# esp32_lolin_clone.net
KiCad netlist of a schematic drawn in EAGLE
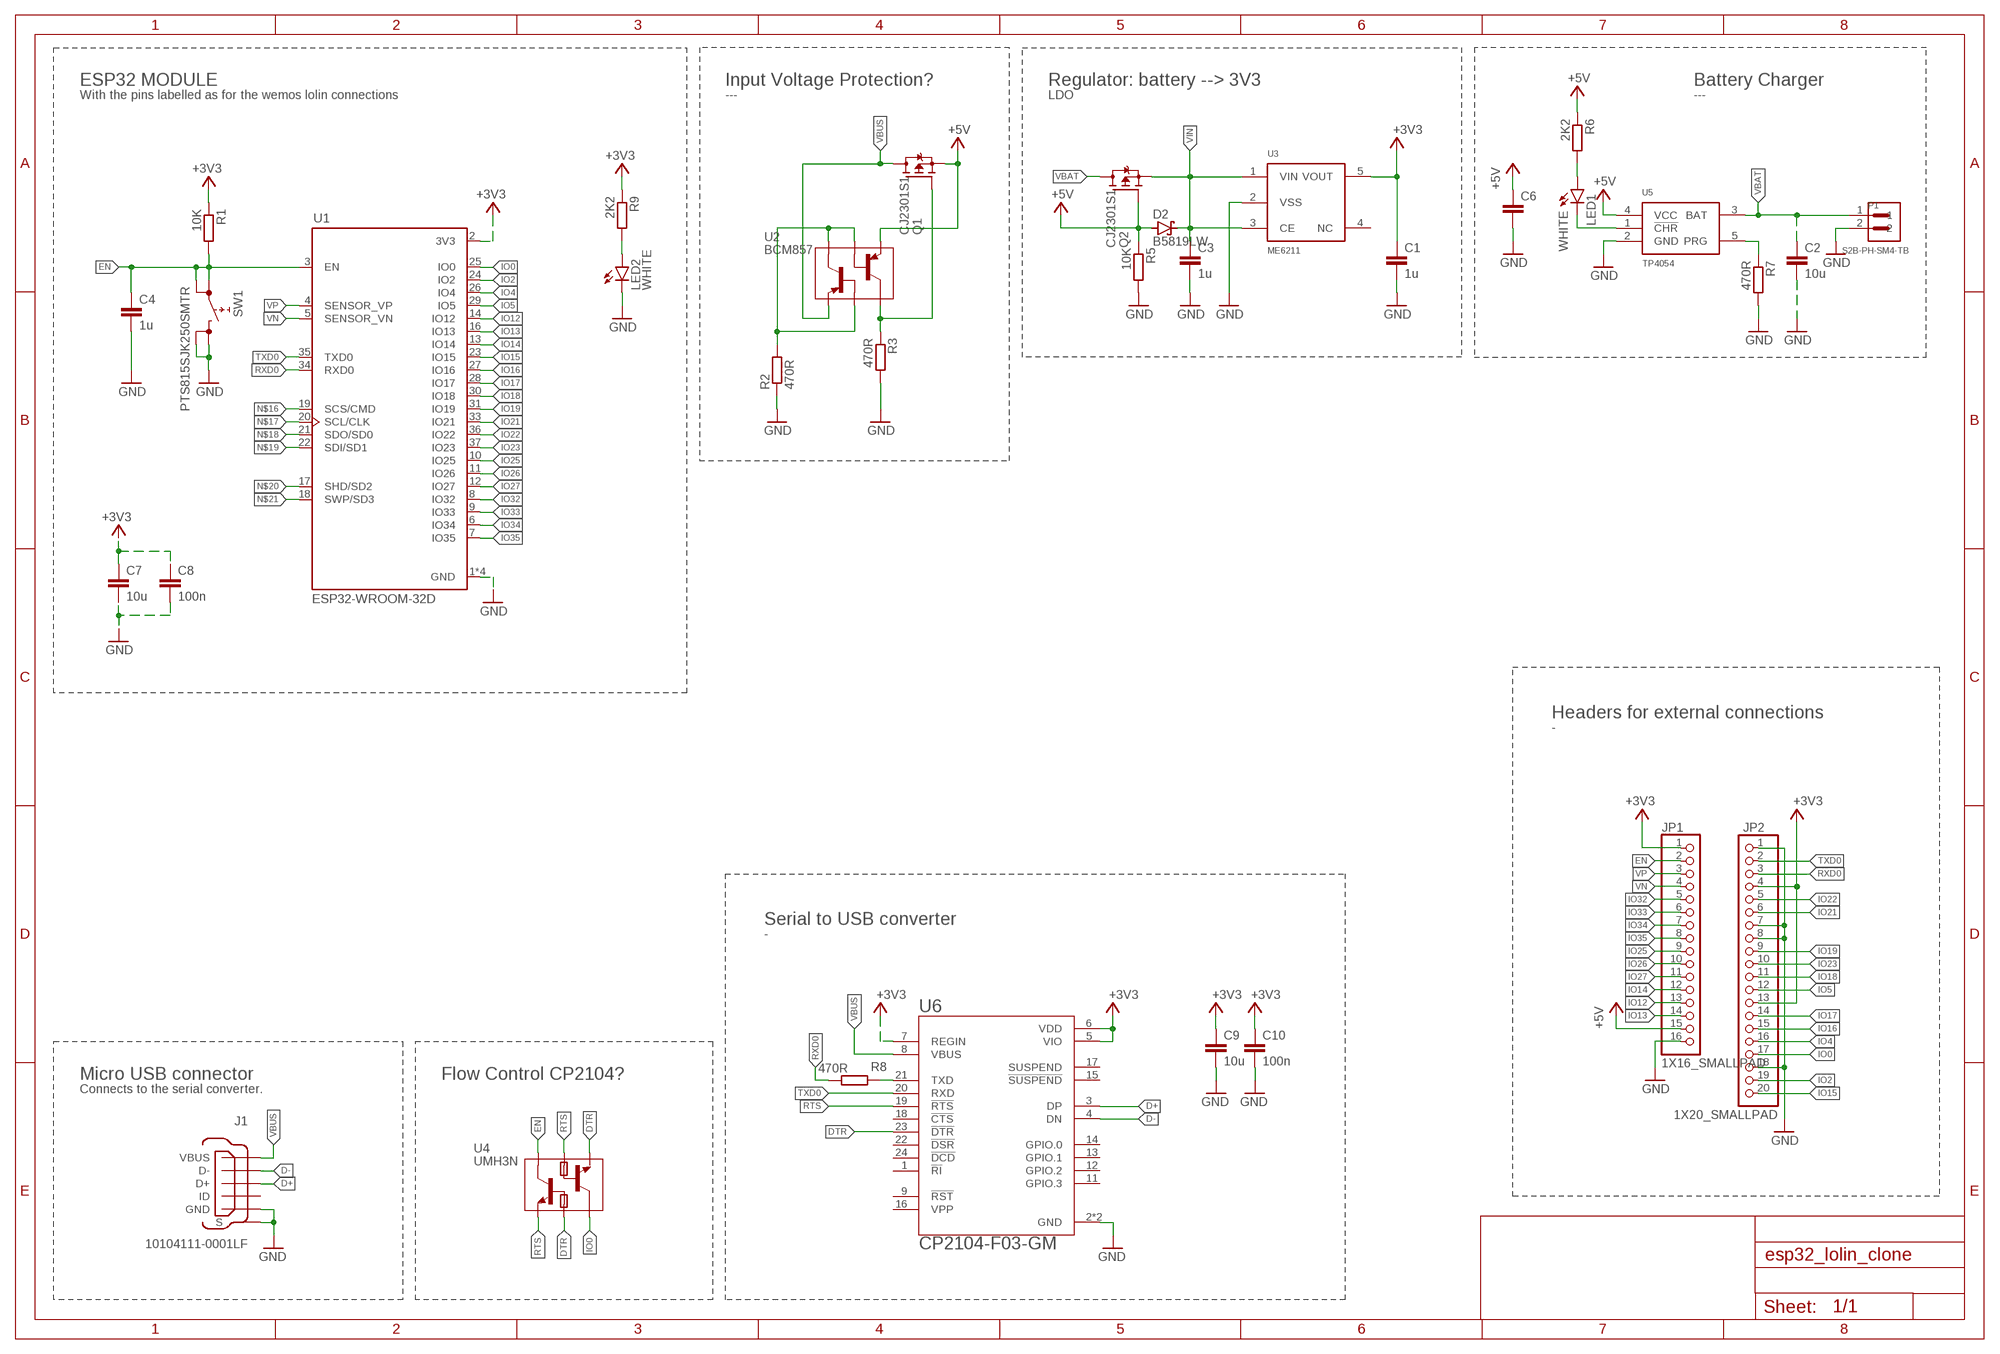
[diagram p0: schematic, sheet 1]

(export (version "E")
  (design (tool "Eeschema 10.0.6"))
  (components
    (comp (ref "C1")
      (value "1u")
      (footprint "eagle-import:C0603K")
      (libsource (lib "eagle-import") (part "C-EUC0603K"))
    )
    (comp (ref "C2")
      (value "10u")
      (footprint "eagle-import:C0603K")
      (libsource (lib "eagle-import") (part "C-EUC0603K"))
    )
    (comp (ref "C3")
      (value "1u")
      (footprint "eagle-import:C0603K")
      (libsource (lib "eagle-import") (part "C-EUC0603K"))
    )
    (comp (ref "C4")
      (value "1u")
      (footprint "eagle-import:C0603K")
      (libsource (lib "eagle-import") (part "C-EUC0603K"))
    )
    (comp (ref "C6")
      (value "C-EUC0603K")
      (footprint "eagle-import:C0603K")
      (libsource (lib "eagle-import") (part "C-EUC0603K"))
    )
    (comp (ref "C7")
      (value "10u")
      (footprint "eagle-import:C0603K")
      (libsource (lib "eagle-import") (part "C-EUC0603K"))
    )
    (comp (ref "C8")
      (value "100n")
      (footprint "eagle-import:C0603K")
      (libsource (lib "eagle-import") (part "C-EUC0603K"))
    )
    (comp (ref "C9")
      (value "10u")
      (footprint "eagle-import:C0603K")
      (libsource (lib "eagle-import") (part "C-EUC0603K"))
    )
    (comp (ref "C10")
      (value "100n")
      (footprint "eagle-import:C0603K")
      (libsource (lib "eagle-import") (part "C-EUC0603K"))
    )
    (comp (ref "D2")
      (value "B5819LW")
      (footprint "eagle-import:SOD123")
      (fields (field (name "MANUFACTURER") "Guangdong Hottech"))
      (libsource (lib "eagle-import") (part "B5819LW"))
    )
    (comp (ref "J1")
      (value "10104111-0001LF")
      (footprint "eagle-import:FRAMATOME_10104111-0001LF")
      (fields (field (name "MANUFACTURER") "Amphenol ICC"))
      (libsource (lib "eagle-import") (part "10104111-0001LF"))
    )
    (comp (ref "JP1")
      (value "1X16_SMALLPAD")
      (footprint "eagle-import:1X16")
      (libsource (lib "eagle-import") (part "1X16_SMALLPAD"))
    )
    (comp (ref "JP2")
      (value "1X20_SMALLPAD")
      (footprint "eagle-import:1X20")
      (libsource (lib "eagle-import") (part "1X20_SMALLPAD"))
    )
    (comp (ref "LED1")
      (value "WHITE")
      (footprint "eagle-import:CHIP-LED0603")
      (libsource (lib "eagle-import") (part "LEDCHIP-LED0603"))
    )
    (comp (ref "LED2")
      (value "WHITE")
      (footprint "eagle-import:CHIP-LED0603")
      (libsource (lib "eagle-import") (part "LEDCHIP-LED0603"))
    )
    (comp (ref "P1")
      (value "S2B-PH-SM4-TB")
      (footprint "eagle-import:JST_S2B-PH-SM4-TB")
      (fields (field (name "MANUFACTURER") "JST Sales"))
      (libsource (lib "eagle-import") (part "S2B-PH-SM4-TB"))
    )
    (comp (ref "Q1")
      (value "CJ2301S1")
      (footprint "eagle-import:SOT23")
      (fields (field (name "MANUFACTURER") "Changjiang Electronics Tech"))
      (libsource (lib "eagle-import") (part "CJ2301S1"))
    )
    (comp (ref "Q2")
      (value "CJ2301S1")
      (footprint "eagle-import:SOT23")
      (fields (field (name "MANUFACTURER") "Changjiang Electronics Tech"))
      (libsource (lib "eagle-import") (part "CJ2301S1"))
    )
    (comp (ref "R1")
      (value "10K")
      (footprint "eagle-import:R0603")
      (libsource (lib "eagle-import") (part "R-EU_R0603"))
    )
    (comp (ref "R2")
      (value "470R")
      (footprint "eagle-import:R0603")
      (libsource (lib "eagle-import") (part "R-EU_R0603"))
    )
    (comp (ref "R3")
      (value "470R")
      (footprint "eagle-import:R0603")
      (libsource (lib "eagle-import") (part "R-EU_R0603"))
    )
    (comp (ref "R5")
      (value "10K")
      (footprint "eagle-import:R0603")
      (libsource (lib "eagle-import") (part "R-EU_R0603"))
    )
    (comp (ref "R6")
      (value "2K2")
      (footprint "eagle-import:R0603")
      (libsource (lib "eagle-import") (part "R-EU_R0603"))
    )
    (comp (ref "R7")
      (value "470R")
      (footprint "eagle-import:R0603")
      (libsource (lib "eagle-import") (part "R-EU_R0603"))
    )
    (comp (ref "R8")
      (value "470R")
      (footprint "eagle-import:R0603")
      (libsource (lib "eagle-import") (part "R-EU_R0603"))
    )
    (comp (ref "R9")
      (value "2K2")
      (footprint "eagle-import:R0603")
      (libsource (lib "eagle-import") (part "R-EU_R0603"))
    )
    (comp (ref "SW1")
      (value "PTS815SJK250SMTR")
      (footprint "eagle-import:PTS815SJK250SMTR")
      (fields (field (name "MANUFACTURER") "C&K"))
      (libsource (lib "eagle-import") (part "PTS815SJK250SMTR"))
    )
    (comp (ref "U1")
      (value "ESP32-WROOM-32D")
      (footprint "eagle-import:MODULE_ESP32-WROOM-32D")
      (fields (field (name "MANUFACTURER") "Espressif Systems"))
      (libsource (lib "eagle-import") (part "ESP32-WROOM-32D"))
    )
    (comp (ref "U2")
      (value "BCM857")
      (footprint "eagle-import:SOT363_INFINEON")
      (fields (field (name "MANUFACTURER") "Nexperia"))
      (libsource (lib "eagle-import") (part "BCM857"))
    )
    (comp (ref "U3")
      (value "ME6211")
      (footprint "eagle-import:SOT23-5")
      (fields (field (name "MANUFACTURER") "MICRONE"))
      (libsource (lib "eagle-import") (part "ME6211"))
    )
    (comp (ref "U4")
      (value "UMH3N")
      (footprint "eagle-import:SOT363_INFINEON")
      (fields (field (name "MANUFACTURER") "Rohm"))
      (libsource (lib "eagle-import") (part "UMH3N"))
    )
    (comp (ref "U5")
      (value "TP4054")
      (footprint "eagle-import:SOT23-5")
      (fields (field (name "MANUFACTURER") "TOPPOWER"))
      (libsource (lib "eagle-import") (part "TP4054"))
    )
    (comp (ref "U6")
      (value "CP2104-F03-GM")
      (footprint "eagle-import:QFN50P400X400X80-25N")
      (fields (field (name "MANUFACTURER") "Silabs"))
      (libsource (lib "eagle-import") (part "CP2104-F03-GM"))
    )
  )
  (nets
    (net (code "1") (name "+3V3") (class "Default")
      (node (ref "C1") (pin "1") (pinfunction "1_1") (pintype "passive"))
      (node (ref "C10") (pin "1") (pinfunction "1_1") (pintype "passive"))
      (node (ref "C7") (pin "1") (pinfunction "1_1") (pintype "passive"))
      (node (ref "C8") (pin "1") (pinfunction "1_1") (pintype "passive"))
      (node (ref "C9") (pin "1") (pinfunction "1_1") (pintype "passive"))
      (node (ref "JP1") (pin "1") (pinfunction "1_1") (pintype "passive"))
      (node (ref "JP2") (pin "13") (pinfunction "13_13") (pintype "passive"))
      (node (ref "JP2") (pin "4") (pinfunction "4_4") (pintype "passive"))
      (node (ref "R1") (pin "1") (pinfunction "1_1") (pintype "passive"))
      (node (ref "R9") (pin "1") (pinfunction "1_1") (pintype "passive"))
      (node (ref "U1") (pin "2") (pinfunction "3V3_2") (pintype "power_in"))
      (node (ref "U3") (pin "5") (pinfunction "VOUT_5") (pintype "bidirectional"))
      (node (ref "U6") (pin "5") (pinfunction "VIO_5") (pintype "power_in"))
      (node (ref "U6") (pin "6") (pinfunction "VDD_6") (pintype "power_in"))
      (node (ref "U6") (pin "7") (pinfunction "REGIN_7") (pintype "input"))
    )
    (net (code "2") (name "+5V") (class "Default")
      (node (ref "C6") (pin "1") (pinfunction "1_1") (pintype "passive"))
      (node (ref "D2") (pin "2") (pinfunction "A_2") (pintype "passive"))
      (node (ref "JP1") (pin "15") (pinfunction "15_15") (pintype "passive"))
      (node (ref "Q1") (pin "2") (pinfunction "S_2") (pintype "passive"))
      (node (ref "Q2") (pin "1") (pinfunction "G_1") (pintype "passive"))
      (node (ref "R5") (pin "1") (pinfunction "1_1") (pintype "passive"))
      (node (ref "R6") (pin "1") (pinfunction "1_1") (pintype "passive"))
      (node (ref "U2") (pin "4") (pinfunction "E2_4") (pintype "passive"))
      (node (ref "U5") (pin "4") (pinfunction "VCC_4") (pintype "bidirectional"))
    )
    (net (code "3") (name "D+") (class "Default")
      (node (ref "J1") (pin "3") (pinfunction "D+_3") (pintype "passive"))
      (node (ref "U6") (pin "3") (pinfunction "DP_3") (pintype "bidirectional"))
    )
    (net (code "4") (name "D-") (class "Default")
      (node (ref "J1") (pin "2") (pinfunction "D-_2") (pintype "passive"))
      (node (ref "U6") (pin "4") (pinfunction "DN_4") (pintype "bidirectional"))
    )
    (net (code "5") (name "DTR") (class "Default")
      (node (ref "U4") (pin "2") (pinfunction "B1_2") (pintype "passive"))
      (node (ref "U4") (pin "4") (pinfunction "E2_4") (pintype "passive"))
      (node (ref "U6") (pin "23") (pinfunction "~{DTR}_23") (pintype "output"))
    )
    (net (code "6") (name "EN") (class "Default")
      (node (ref "C4") (pin "1") (pinfunction "1_1") (pintype "passive"))
      (node (ref "JP1") (pin "2") (pinfunction "2_2") (pintype "passive"))
      (node (ref "R1") (pin "2") (pinfunction "2_2") (pintype "passive"))
      (node (ref "SW1") (pin "1") (pinfunction "0_1") (pintype "passive"))
      (node (ref "SW1") (pin "2") (pinfunction "0_2") (pintype "passive"))
      (node (ref "U1") (pin "3") (pinfunction "EN_3") (pintype "input"))
      (node (ref "U4") (pin "6") (pinfunction "C1_6") (pintype "passive"))
    )
    (net (code "7") (name "GND") (class "Default")
      (node (ref "C1") (pin "2") (pinfunction "2_2") (pintype "passive"))
      (node (ref "C10") (pin "2") (pinfunction "2_2") (pintype "passive"))
      (node (ref "C2") (pin "2") (pinfunction "2_2") (pintype "passive"))
      (node (ref "C3") (pin "2") (pinfunction "2_2") (pintype "passive"))
      (node (ref "C4") (pin "2") (pinfunction "2_2") (pintype "passive"))
      (node (ref "C6") (pin "2") (pinfunction "2_2") (pintype "passive"))
      (node (ref "C7") (pin "2") (pinfunction "2_2") (pintype "passive"))
      (node (ref "C8") (pin "2") (pinfunction "2_2") (pintype "passive"))
      (node (ref "C9") (pin "2") (pinfunction "2_2") (pintype "passive"))
      (node (ref "J1") (pin "5") (pinfunction "GND_5") (pintype "power_in"))
      (node (ref "J1") (pin "6") (pinfunction "S_6") (pintype "power_in"))
      (node (ref "J1") (pin "7") (pinfunction "S_7") (pintype "power_in"))
      (node (ref "J1") (pin "8") (pinfunction "S_8") (pintype "power_in"))
      (node (ref "J1") (pin "9") (pinfunction "S_9") (pintype "power_in"))
      (node (ref "JP1") (pin "16") (pinfunction "16_16") (pintype "passive"))
      (node (ref "JP2") (pin "1") (pinfunction "1_1") (pintype "passive"))
      (node (ref "JP2") (pin "18") (pinfunction "18_18") (pintype "passive"))
      (node (ref "JP2") (pin "7") (pinfunction "7_7") (pintype "passive"))
      (node (ref "JP2") (pin "8") (pinfunction "8_8") (pintype "passive"))
      (node (ref "LED2") (pin "C") (pinfunction "C_C") (pintype "passive"))
      (node (ref "P1") (pin "2") (pinfunction "2_2") (pintype "passive"))
      (node (ref "R2") (pin "1") (pinfunction "1_1") (pintype "passive"))
      (node (ref "R3") (pin "2") (pinfunction "2_2") (pintype "passive"))
      (node (ref "R5") (pin "2") (pinfunction "2_2") (pintype "passive"))
      (node (ref "R7") (pin "2") (pinfunction "2_2") (pintype "passive"))
      (node (ref "SW1") (pin "3") (pinfunction "1_3") (pintype "passive"))
      (node (ref "SW1") (pin "4") (pinfunction "1_4") (pintype "passive"))
      (node (ref "U1") (pin "1") (pinfunction "GND_1") (pintype "power_in"))
      (node (ref "U1") (pin "15") (pinfunction "GND_15") (pintype "power_in"))
      (node (ref "U1") (pin "38") (pinfunction "GND_38") (pintype "power_in"))
      (node (ref "U1") (pin "39") (pinfunction "GND_39") (pintype "power_in"))
      (node (ref "U3") (pin "2") (pinfunction "VSS_2") (pintype "bidirectional"))
      (node (ref "U5") (pin "2") (pinfunction "GND_2") (pintype "bidirectional"))
      (node (ref "U6") (pin "2") (pinfunction "GND_2") (pintype "power_in"))
      (node (ref "U6") (pin "25") (pinfunction "GND_25") (pintype "power_in"))
    )
    (net (code "8") (name "IO0") (class "Default")
      (node (ref "JP2") (pin "17") (pinfunction "17_17") (pintype "passive"))
      (node (ref "U1") (pin "25") (pinfunction "IO0_25") (pintype "bidirectional"))
      (node (ref "U4") (pin "3") (pinfunction "C2_3") (pintype "passive"))
    )
    (net (code "9") (name "IO2") (class "Default")
      (node (ref "JP2") (pin "19") (pinfunction "19_19") (pintype "passive"))
      (node (ref "U1") (pin "24") (pinfunction "IO2_24") (pintype "bidirectional"))
    )
    (net (code "10") (name "IO4") (class "Default")
      (node (ref "JP2") (pin "16") (pinfunction "16_16") (pintype "passive"))
      (node (ref "U1") (pin "26") (pinfunction "IO4_26") (pintype "bidirectional"))
    )
    (net (code "11") (name "IO5") (class "Default")
      (node (ref "JP2") (pin "12") (pinfunction "12_12") (pintype "passive"))
      (node (ref "U1") (pin "29") (pinfunction "IO5_29") (pintype "bidirectional"))
    )
    (net (code "12") (name "IO12") (class "Default")
      (node (ref "JP1") (pin "13") (pinfunction "13_13") (pintype "passive"))
      (node (ref "U1") (pin "14") (pinfunction "IO12_14") (pintype "bidirectional"))
    )
    (net (code "13") (name "IO13") (class "Default")
      (node (ref "JP1") (pin "14") (pinfunction "14_14") (pintype "passive"))
      (node (ref "U1") (pin "16") (pinfunction "IO13_16") (pintype "bidirectional"))
    )
    (net (code "14") (name "IO14") (class "Default")
      (node (ref "JP1") (pin "12") (pinfunction "12_12") (pintype "passive"))
      (node (ref "U1") (pin "13") (pinfunction "IO14_13") (pintype "bidirectional"))
    )
    (net (code "15") (name "IO15") (class "Default")
      (node (ref "JP2") (pin "20") (pinfunction "20_20") (pintype "passive"))
      (node (ref "U1") (pin "23") (pinfunction "IO15_23") (pintype "bidirectional"))
    )
    (net (code "16") (name "IO16") (class "Default")
      (node (ref "JP2") (pin "15") (pinfunction "15_15") (pintype "passive"))
      (node (ref "U1") (pin "27") (pinfunction "IO16_27") (pintype "bidirectional"))
    )
    (net (code "17") (name "IO17") (class "Default")
      (node (ref "JP2") (pin "14") (pinfunction "14_14") (pintype "passive"))
      (node (ref "U1") (pin "28") (pinfunction "IO17_28") (pintype "bidirectional"))
    )
    (net (code "18") (name "IO18") (class "Default")
      (node (ref "JP2") (pin "11") (pinfunction "11_11") (pintype "passive"))
      (node (ref "U1") (pin "30") (pinfunction "IO18_30") (pintype "bidirectional"))
    )
    (net (code "19") (name "IO19") (class "Default")
      (node (ref "JP2") (pin "9") (pinfunction "9_9") (pintype "passive"))
      (node (ref "U1") (pin "31") (pinfunction "IO19_31") (pintype "bidirectional"))
    )
    (net (code "20") (name "IO21") (class "Default")
      (node (ref "JP2") (pin "6") (pinfunction "6_6") (pintype "passive"))
      (node (ref "U1") (pin "33") (pinfunction "IO21_33") (pintype "bidirectional"))
    )
    (net (code "21") (name "IO22") (class "Default")
      (node (ref "JP2") (pin "5") (pinfunction "5_5") (pintype "passive"))
      (node (ref "U1") (pin "36") (pinfunction "IO22_36") (pintype "bidirectional"))
    )
    (net (code "22") (name "IO23") (class "Default")
      (node (ref "JP2") (pin "10") (pinfunction "10_10") (pintype "passive"))
      (node (ref "U1") (pin "37") (pinfunction "IO23_37") (pintype "bidirectional"))
    )
    (net (code "23") (name "IO25") (class "Default")
      (node (ref "JP1") (pin "9") (pinfunction "9_9") (pintype "passive"))
      (node (ref "U1") (pin "10") (pinfunction "IO25_10") (pintype "bidirectional"))
    )
    (net (code "24") (name "IO26") (class "Default")
      (node (ref "JP1") (pin "10") (pinfunction "10_10") (pintype "passive"))
      (node (ref "U1") (pin "11") (pinfunction "IO26_11") (pintype "bidirectional"))
    )
    (net (code "25") (name "IO27") (class "Default")
      (node (ref "JP1") (pin "11") (pinfunction "11_11") (pintype "passive"))
      (node (ref "U1") (pin "12") (pinfunction "IO27_12") (pintype "bidirectional"))
    )
    (net (code "26") (name "IO32") (class "Default")
      (node (ref "JP1") (pin "5") (pinfunction "5_5") (pintype "passive"))
      (node (ref "U1") (pin "8") (pinfunction "IO32_8") (pintype "bidirectional"))
    )
    (net (code "27") (name "IO33") (class "Default")
      (node (ref "JP1") (pin "6") (pinfunction "6_6") (pintype "passive"))
      (node (ref "U1") (pin "9") (pinfunction "IO33_9") (pintype "bidirectional"))
    )
    (net (code "28") (name "IO34") (class "Default")
      (node (ref "JP1") (pin "7") (pinfunction "7_7") (pintype "passive"))
      (node (ref "U1") (pin "6") (pinfunction "IO34_6") (pintype "bidirectional"))
    )
    (net (code "29") (name "IO35") (class "Default")
      (node (ref "JP1") (pin "8") (pinfunction "8_8") (pintype "passive"))
      (node (ref "U1") (pin "7") (pinfunction "IO35_7") (pintype "bidirectional"))
    )
    (net (code "30") (name "N$16") (class "Default")
      (node (ref "U1") (pin "19") (pinfunction "SCS/CMD_19") (pintype "bidirectional"))
    )
    (net (code "31") (name "N$17") (class "Default")
      (node (ref "U1") (pin "20") (pinfunction "SCL/CLK_20") (pintype "bidirectional"))
    )
    (net (code "32") (name "N$18") (class "Default")
      (node (ref "U1") (pin "21") (pinfunction "SDO/SD0_21") (pintype "bidirectional"))
    )
    (net (code "33") (name "N$19") (class "Default")
      (node (ref "U1") (pin "22") (pinfunction "SDI/SD1_22") (pintype "bidirectional"))
    )
    (net (code "34") (name "N$20") (class "Default")
      (node (ref "U1") (pin "17") (pinfunction "SHD/SD2_17") (pintype "bidirectional"))
    )
    (net (code "35") (name "N$21") (class "Default")
      (node (ref "U1") (pin "18") (pinfunction "SWP/SD3_18") (pintype "bidirectional"))
    )
    (net (code "36") (name "Net-(LED1-PadA)") (class "Default")
      (node (ref "LED1") (pin "A") (pinfunction "A_A") (pintype "passive"))
      (node (ref "R6") (pin "2") (pinfunction "2_2") (pintype "passive"))
    )
    (net (code "37") (name "Net-(LED2-PadA)") (class "Default")
      (node (ref "LED2") (pin "A") (pinfunction "A_A") (pintype "passive"))
      (node (ref "R9") (pin "2") (pinfunction "2_2") (pintype "passive"))
    )
    (net (code "38") (name "Net-(Q1-G)") (class "Default")
      (node (ref "Q1") (pin "1") (pinfunction "G_1") (pintype "passive"))
      (node (ref "R3") (pin "1") (pinfunction "1_1") (pintype "passive"))
      (node (ref "U2") (pin "3") (pinfunction "C2_3") (pintype "passive"))
    )
    (net (code "39") (name "Net-(U2-B1)") (class "Default")
      (node (ref "R2") (pin "2") (pinfunction "2_2") (pintype "passive"))
      (node (ref "U2") (pin "2") (pinfunction "B1_2") (pintype "passive"))
      (node (ref "U2") (pin "5") (pinfunction "B2_5") (pintype "passive"))
      (node (ref "U2") (pin "6") (pinfunction "C1_6") (pintype "passive"))
    )
    (net (code "40") (name "Net-(U5-PRG)") (class "Default")
      (node (ref "R7") (pin "1") (pinfunction "1_1") (pintype "passive"))
      (node (ref "U5") (pin "5") (pinfunction "PRG_5") (pintype "bidirectional"))
    )
    (net (code "41") (name "Net-(U5-~{CHR})") (class "Default")
      (node (ref "LED1") (pin "C") (pinfunction "C_C") (pintype "passive"))
      (node (ref "U5") (pin "1") (pinfunction "~{CHR}_1") (pintype "bidirectional"))
    )
    (net (code "42") (name "Net-(U6-TXD)") (class "Default")
      (node (ref "R8") (pin "1") (pinfunction "1_1") (pintype "passive"))
      (node (ref "U6") (pin "21") (pinfunction "TXD_21") (pintype "output"))
    )
    (net (code "43") (name "RTS") (class "Default")
      (node (ref "U4") (pin "1") (pinfunction "E1_1") (pintype "passive"))
      (node (ref "U4") (pin "5") (pinfunction "B2_5") (pintype "passive"))
      (node (ref "U6") (pin "19") (pinfunction "~{RTS}_19") (pintype "output"))
    )
    (net (code "44") (name "RXD0") (class "Default")
      (node (ref "JP2") (pin "3") (pinfunction "3_3") (pintype "passive"))
      (node (ref "R8") (pin "2") (pinfunction "2_2") (pintype "passive"))
      (node (ref "U1") (pin "34") (pinfunction "RXD0_34") (pintype "bidirectional"))
    )
    (net (code "45") (name "TXD0") (class "Default")
      (node (ref "JP2") (pin "2") (pinfunction "2_2") (pintype "passive"))
      (node (ref "U1") (pin "35") (pinfunction "TXD0_35") (pintype "bidirectional"))
      (node (ref "U6") (pin "20") (pinfunction "RXD_20") (pintype "input"))
    )
    (net (code "46") (name "VBAT") (class "Default")
      (node (ref "C2") (pin "1") (pinfunction "1_1") (pintype "passive"))
      (node (ref "P1") (pin "1") (pinfunction "1_1") (pintype "passive"))
      (node (ref "Q2") (pin "3") (pinfunction "D_3") (pintype "passive"))
      (node (ref "U5") (pin "3") (pinfunction "BAT_3") (pintype "bidirectional"))
    )
    (net (code "47") (name "VBUS") (class "Default")
      (node (ref "J1") (pin "1") (pinfunction "VBUS_1") (pintype "power_in"))
      (node (ref "Q1") (pin "3") (pinfunction "D_3") (pintype "passive"))
      (node (ref "U2") (pin "1") (pinfunction "E1_1") (pintype "passive"))
      (node (ref "U6") (pin "8") (pinfunction "VBUS_8") (pintype "input"))
    )
    (net (code "48") (name "VIN") (class "Default")
      (node (ref "C3") (pin "1") (pinfunction "1_1") (pintype "passive"))
      (node (ref "D2") (pin "1") (pinfunction "C_1") (pintype "passive"))
      (node (ref "Q2") (pin "2") (pinfunction "S_2") (pintype "passive"))
      (node (ref "U3") (pin "1") (pinfunction "VIN_1") (pintype "bidirectional"))
      (node (ref "U3") (pin "3") (pinfunction "CE_3") (pintype "bidirectional"))
    )
    (net (code "49") (name "VN") (class "Default")
      (node (ref "JP1") (pin "4") (pinfunction "4_4") (pintype "passive"))
      (node (ref "U1") (pin "5") (pinfunction "SENSOR_VN_5") (pintype "input"))
    )
    (net (code "50") (name "VP") (class "Default")
      (node (ref "JP1") (pin "3") (pinfunction "3_3") (pintype "passive"))
      (node (ref "U1") (pin "4") (pinfunction "SENSOR_VP_4") (pintype "input"))
    )
    (net (code "51") (name "unconnected-(J1-ID-Pad4)") (class "Default")
      (node (ref "J1") (pin "4") (pinfunction "ID_4") (pintype "passive"))
    )
    (net (code "52") (name "unconnected-(U3-NC-Pad4)") (class "Default")
      (node (ref "U3") (pin "4") (pinfunction "NC_4") (pintype "bidirectional"))
    )
    (net (code "53") (name "unconnected-(U6-GPIO.0-Pad14)") (class "Default")
      (node (ref "U6") (pin "14") (pinfunction "GPIO.0_14") (pintype "bidirectional"))
    )
    (net (code "54") (name "unconnected-(U6-GPIO.1-Pad13)") (class "Default")
      (node (ref "U6") (pin "13") (pinfunction "GPIO.1_13") (pintype "bidirectional"))
    )
    (net (code "55") (name "unconnected-(U6-GPIO.2-Pad12)") (class "Default")
      (node (ref "U6") (pin "12") (pinfunction "GPIO.2_12") (pintype "bidirectional"))
    )
    (net (code "56") (name "unconnected-(U6-GPIO.3-Pad11)") (class "Default")
      (node (ref "U6") (pin "11") (pinfunction "GPIO.3_11") (pintype "bidirectional"))
    )
    (net (code "57") (name "unconnected-(U6-SUSPEND-Pad17)") (class "Default")
      (node (ref "U6") (pin "17") (pinfunction "SUSPEND_17") (pintype "output"))
    )
    (net (code "58") (name "unconnected-(U6-VPP-Pad16)") (class "Default")
      (node (ref "U6") (pin "16") (pinfunction "VPP_16") (pintype "passive"))
    )
    (net (code "59") (name "unconnected-(U6-~{CTS}-Pad18)") (class "Default")
      (node (ref "U6") (pin "18") (pinfunction "~{CTS}_18") (pintype "input"))
    )
    (net (code "60") (name "unconnected-(U6-~{DCD}-Pad24)") (class "Default")
      (node (ref "U6") (pin "24") (pinfunction "~{DCD}_24") (pintype "input"))
    )
    (net (code "61") (name "unconnected-(U6-~{DSR}-Pad22)") (class "Default")
      (node (ref "U6") (pin "22") (pinfunction "~{DSR}_22") (pintype "input"))
    )
    (net (code "62") (name "unconnected-(U6-~{RI}-Pad1)") (class "Default")
      (node (ref "U6") (pin "1") (pinfunction "~{RI}_1") (pintype "input"))
    )
    (net (code "63") (name "unconnected-(U6-~{RST}-Pad9)") (class "Default")
      (node (ref "U6") (pin "9") (pinfunction "~{RST}_9") (pintype "bidirectional"))
    )
    (net (code "64") (name "unconnected-(U6-~{SUSPEND}-Pad15)") (class "Default")
      (node (ref "U6") (pin "15") (pinfunction "~{SUSPEND}_15") (pintype "output"))
    )
  )
)
